# Digital_Isolator.net
KiCad netlist of a schematic drawn in Altium Designer
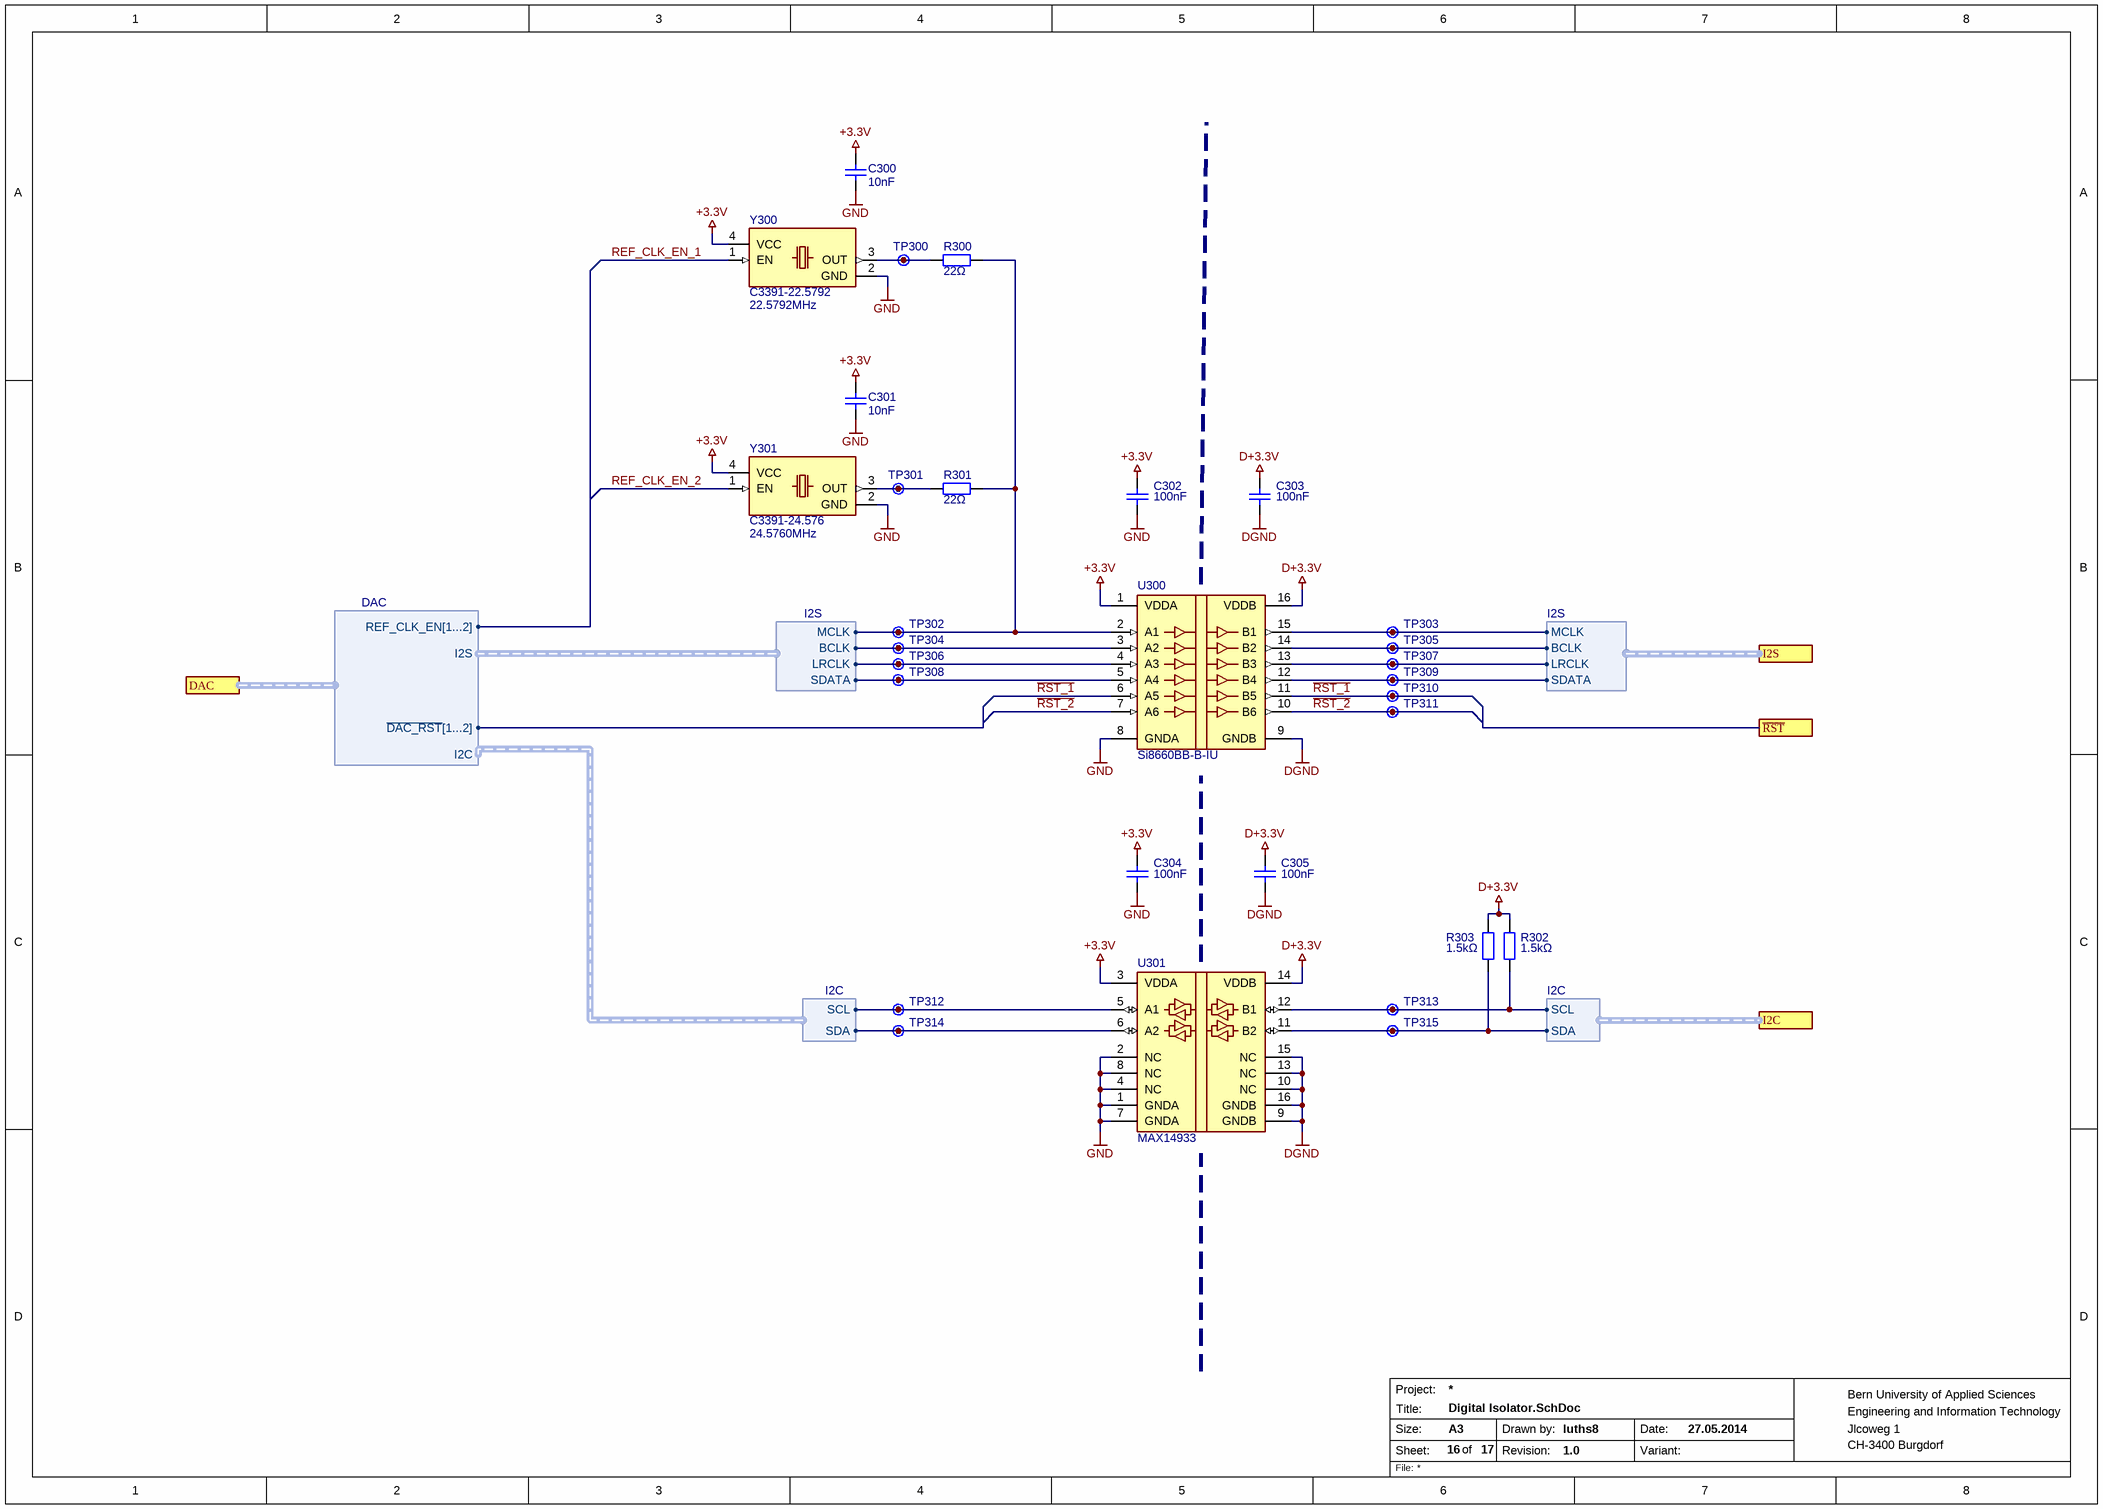
[diagram p0: Digital Isolator.SchDoc]

(export (version "E")
  (design (tool "Eeschema 10.0.6"))
  (components
    (comp (ref "C300")
      (value "10nF")
      (footprint "SMD0603CAP")
      (description "Ceramic Capacitor")
      (libsource (lib "Audio-Streamer") (part "Capacitor Ceramic"))
    )
    (comp (ref "C301")
      (value "10nF")
      (footprint "SMD0603CAP")
      (description "Ceramic Capacitor")
      (libsource (lib "Audio-Streamer") (part "Capacitor Ceramic"))
    )
    (comp (ref "C302")
      (value "100nF")
      (footprint "SMD0603CAP")
      (description "Ceramic Capacitor")
      (libsource (lib "Audio-Streamer") (part "Capacitor Ceramic"))
    )
    (comp (ref "C303")
      (value "100nF")
      (footprint "SMD0603CAP")
      (description "Ceramic Capacitor")
      (libsource (lib "Audio-Streamer") (part "Capacitor Ceramic"))
    )
    (comp (ref "C304")
      (value "100nF")
      (footprint "SMD0603CAP")
      (description "Ceramic Capacitor")
      (libsource (lib "Audio-Streamer") (part "Capacitor Ceramic"))
    )
    (comp (ref "C305")
      (value "100nF")
      (footprint "SMD0603CAP")
      (description "Ceramic Capacitor")
      (libsource (lib "Audio-Streamer") (part "Capacitor Ceramic"))
    )
    (comp (ref "R300")
      (value "22Ω")
      (footprint "SMD0603RES")
      (description "Resistor")
      (libsource (lib "") (part "Resistor_1"))
    )
    (comp (ref "R301")
      (value "22Ω")
      (footprint "SMD0603RES")
      (description "Resistor")
      (libsource (lib "") (part "Resistor_1"))
    )
    (comp (ref "R302")
      (value "1.5kΩ")
      (footprint "SMD0603RES")
      (description "Resistor")
      (libsource (lib "Audio-Streamer") (part "Resistor"))
    )
    (comp (ref "R303")
      (value "1.5kΩ")
      (footprint "SMD0603RES")
      (description "Resistor")
      (libsource (lib "Audio-Streamer") (part "Resistor"))
    )
    (comp (ref "TP300")
      (value "Testpoint")
      (footprint "TP")
      (libsource (lib "Audio-Streamer") (part "Testpoint"))
    )
    (comp (ref "TP301")
      (value "Testpoint")
      (footprint "TP")
      (libsource (lib "Audio-Streamer") (part "Testpoint"))
    )
    (comp (ref "TP302")
      (value "Testpoint")
      (footprint "TP")
      (libsource (lib "Audio-Streamer") (part "Testpoint"))
    )
    (comp (ref "TP303")
      (value "Testpoint")
      (footprint "TP")
      (libsource (lib "Audio-Streamer") (part "Testpoint"))
    )
    (comp (ref "TP304")
      (value "Testpoint")
      (footprint "TP")
      (libsource (lib "Audio-Streamer") (part "Testpoint"))
    )
    (comp (ref "TP305")
      (value "Testpoint")
      (footprint "TP")
      (libsource (lib "Audio-Streamer") (part "Testpoint"))
    )
    (comp (ref "TP306")
      (value "Testpoint")
      (footprint "TP")
      (libsource (lib "Audio-Streamer") (part "Testpoint"))
    )
    (comp (ref "TP307")
      (value "Testpoint")
      (footprint "TP")
      (libsource (lib "Audio-Streamer") (part "Testpoint"))
    )
    (comp (ref "TP308")
      (value "Testpoint")
      (footprint "TP")
      (libsource (lib "Audio-Streamer") (part "Testpoint"))
    )
    (comp (ref "TP309")
      (value "Testpoint")
      (footprint "TP")
      (libsource (lib "Audio-Streamer") (part "Testpoint"))
    )
    (comp (ref "TP310")
      (value "Testpoint")
      (footprint "TP")
      (libsource (lib "Audio-Streamer") (part "Testpoint"))
    )
    (comp (ref "TP311")
      (value "Testpoint")
      (footprint "TP")
      (libsource (lib "Audio-Streamer") (part "Testpoint"))
    )
    (comp (ref "TP312")
      (value "Testpoint")
      (footprint "TP")
      (libsource (lib "Audio-Streamer") (part "Testpoint"))
    )
    (comp (ref "TP313")
      (value "Testpoint")
      (footprint "TP")
      (libsource (lib "Audio-Streamer") (part "Testpoint"))
    )
    (comp (ref "TP314")
      (value "Testpoint")
      (footprint "TP")
      (libsource (lib "Audio-Streamer") (part "Testpoint"))
    )
    (comp (ref "TP315")
      (value "Testpoint")
      (footprint "TP")
      (libsource (lib "Audio-Streamer") (part "Testpoint"))
    )
    (comp (ref "U300")
      (value "Si8660BB-B-IU")
      (footprint "SOIC16WIDE")
      (description "Unidirectional digital isolator")
      (libsource (lib "Audio-Streamer") (part "Si8660BB-B-IU"))
    )
    (comp (ref "U301")
      (value "MAX14933")
      (footprint "SOIC16WIDE")
      (description "Bidirectional digital isolator")
      (libsource (lib "Audio-Streamer") (part "MAX14933"))
    )
    (comp (ref "Y300")
      (value "C3391-22.5792")
      (footprint "OSC_CRYSTEK")
      (description "HCMOS Oscillator")
      (fields (field (name "FREQUENCY") "22.5792MHz"))
      (libsource (lib "Audio-Streamer") (part "Oscillator Crystek"))
    )
    (comp (ref "Y301")
      (value "C3391-24.576")
      (footprint "OSC_CRYSTEK")
      (description "HCMOS Oscillator")
      (fields (field (name "FREQUENCY") "24.5760MHz"))
      (libsource (lib "Audio-Streamer") (part "Oscillator Crystek"))
    )
  )
  (nets
    (net (code "4") (name "+3.3V") (class "Default")
      (node (ref "C300") (pin "1") (pinfunction "1_1") (pintype "passive"))
      (node (ref "C301") (pin "1") (pinfunction "1_1") (pintype "passive"))
      (node (ref "C302") (pin "1") (pinfunction "1_1") (pintype "passive"))
      (node (ref "C304") (pin "1") (pinfunction "1_1") (pintype "passive"))
      (node (ref "U300") (pin "1") (pinfunction "VDDA_1") (pintype "power_in"))
      (node (ref "U301") (pin "3") (pinfunction "VDDA_3") (pintype "power_in"))
      (node (ref "Y300") (pin "4") (pinfunction "VCC_4") (pintype "power_in"))
      (node (ref "Y301") (pin "4") (pinfunction "VCC_4") (pintype "power_in"))
    )
    (net (code "6") (name "/REF_CLK_EN_1") (class "Default")
      (node (ref "Y300") (pin "1") (pinfunction "EN_1") (pintype "input"))
    )
    (net (code "7") (name "/REF_CLK_EN_2") (class "Default")
      (node (ref "Y301") (pin "1") (pinfunction "EN_1") (pintype "input"))
    )
    (net (code "10") (name "/~{RST_1}") (class "Default")
      (node (ref "TP310") (pin "1") (pinfunction "1_1") (pintype "passive"))
      (node (ref "U300") (pin "11") (pinfunction "B5_11") (pintype "output"))
      (node (ref "U300") (pin "6") (pinfunction "A5_6") (pintype "input"))
    )
    (net (code "11") (name "/~{RST_2}") (class "Default")
      (node (ref "TP311") (pin "1") (pinfunction "1_1") (pintype "passive"))
      (node (ref "U300") (pin "10") (pinfunction "B6_10") (pintype "output"))
      (node (ref "U300") (pin "7") (pinfunction "A6_7") (pintype "input"))
    )
    (net (code "13") (name "D+3.3V") (class "Default")
      (node (ref "C303") (pin "1") (pinfunction "1_1") (pintype "passive"))
      (node (ref "C305") (pin "1") (pinfunction "1_1") (pintype "passive"))
      (node (ref "R302") (pin "2") (pinfunction "2_2") (pintype "passive"))
      (node (ref "R303") (pin "2") (pinfunction "2_2") (pintype "passive"))
      (node (ref "U300") (pin "16") (pinfunction "VDDB_16") (pintype "power_in"))
      (node (ref "U301") (pin "14") (pinfunction "VDDB_14") (pintype "power_in"))
    )
    (net (code "14") (name "DGND") (class "Default")
      (node (ref "C303") (pin "2") (pinfunction "q_2") (pintype "passive"))
      (node (ref "C305") (pin "2") (pinfunction "q_2") (pintype "passive"))
      (node (ref "U300") (pin "9") (pinfunction "GNDB_9") (pintype "power_in"))
      (node (ref "U301") (pin "10") (pinfunction "NC_10") (pintype "passive"))
      (node (ref "U301") (pin "13") (pinfunction "NC_13") (pintype "passive"))
      (node (ref "U301") (pin "15") (pinfunction "NC_15") (pintype "passive"))
      (node (ref "U301") (pin "16") (pinfunction "GNDB_16") (pintype "power_in"))
      (node (ref "U301") (pin "9") (pinfunction "GNDB_9") (pintype "power_in"))
    )
    (net (code "15") (name "GND") (class "Default")
      (node (ref "C300") (pin "2") (pinfunction "q_2") (pintype "passive"))
      (node (ref "C301") (pin "2") (pinfunction "q_2") (pintype "passive"))
      (node (ref "C302") (pin "2") (pinfunction "q_2") (pintype "passive"))
      (node (ref "C304") (pin "2") (pinfunction "q_2") (pintype "passive"))
      (node (ref "U300") (pin "8") (pinfunction "GNDA_8") (pintype "power_in"))
      (node (ref "U301") (pin "1") (pinfunction "GNDA_1") (pintype "power_in"))
      (node (ref "U301") (pin "2") (pinfunction "NC_2") (pintype "passive"))
      (node (ref "U301") (pin "4") (pinfunction "NC_4") (pintype "passive"))
      (node (ref "U301") (pin "7") (pinfunction "GNDA_7") (pintype "power_in"))
      (node (ref "U301") (pin "8") (pinfunction "NC_8") (pintype "passive"))
      (node (ref "Y300") (pin "2") (pinfunction "GND_2") (pintype "power_in"))
      (node (ref "Y301") (pin "2") (pinfunction "GND_2") (pintype "power_in"))
    )
    (net (code "16") (name "Net-(U300-A1)") (class "Default")
      (node (ref "R300") (pin "2") (pinfunction "2_2") (pintype "passive"))
      (node (ref "R301") (pin "2") (pinfunction "2_2") (pintype "passive"))
      (node (ref "TP302") (pin "1") (pinfunction "1_1") (pintype "passive"))
      (node (ref "U300") (pin "2") (pinfunction "A1_2") (pintype "input"))
    )
    (net (code "17") (name "Net-(U300-A2)") (class "Default")
      (node (ref "TP304") (pin "1") (pinfunction "1_1") (pintype "passive"))
      (node (ref "U300") (pin "3") (pinfunction "A2_3") (pintype "input"))
    )
    (net (code "18") (name "Net-(U300-A3)") (class "Default")
      (node (ref "TP306") (pin "1") (pinfunction "1_1") (pintype "passive"))
      (node (ref "U300") (pin "4") (pinfunction "A3_4") (pintype "input"))
    )
    (net (code "19") (name "Net-(U300-A4)") (class "Default")
      (node (ref "TP308") (pin "1") (pinfunction "1_1") (pintype "passive"))
      (node (ref "U300") (pin "5") (pinfunction "A4_5") (pintype "input"))
    )
    (net (code "20") (name "Net-(U300-B1)") (class "Default")
      (node (ref "TP303") (pin "1") (pinfunction "1_1") (pintype "passive"))
      (node (ref "U300") (pin "15") (pinfunction "B1_15") (pintype "output"))
    )
    (net (code "21") (name "Net-(U300-B2)") (class "Default")
      (node (ref "TP305") (pin "1") (pinfunction "1_1") (pintype "passive"))
      (node (ref "U300") (pin "14") (pinfunction "B2_14") (pintype "output"))
    )
    (net (code "22") (name "Net-(U300-B3)") (class "Default")
      (node (ref "TP307") (pin "1") (pinfunction "1_1") (pintype "passive"))
      (node (ref "U300") (pin "13") (pinfunction "B3_13") (pintype "output"))
    )
    (net (code "23") (name "Net-(U300-B4)") (class "Default")
      (node (ref "TP309") (pin "1") (pinfunction "1_1") (pintype "passive"))
      (node (ref "U300") (pin "12") (pinfunction "B4_12") (pintype "output"))
    )
    (net (code "24") (name "Net-(U301-A1)") (class "Default")
      (node (ref "TP312") (pin "1") (pinfunction "1_1") (pintype "passive"))
      (node (ref "U301") (pin "5") (pinfunction "A1_5") (pintype "bidirectional"))
    )
    (net (code "25") (name "Net-(U301-A2)") (class "Default")
      (node (ref "TP314") (pin "1") (pinfunction "1_1") (pintype "passive"))
      (node (ref "U301") (pin "6") (pinfunction "A2_6") (pintype "bidirectional"))
    )
    (net (code "26") (name "Net-(U301-B1)") (class "Default")
      (node (ref "R302") (pin "1") (pinfunction "1_1") (pintype "passive"))
      (node (ref "TP313") (pin "1") (pinfunction "1_1") (pintype "passive"))
      (node (ref "U301") (pin "12") (pinfunction "B1_12") (pintype "bidirectional"))
    )
    (net (code "27") (name "Net-(U301-B2)") (class "Default")
      (node (ref "R303") (pin "1") (pinfunction "1_1") (pintype "passive"))
      (node (ref "TP315") (pin "1") (pinfunction "1_1") (pintype "passive"))
      (node (ref "U301") (pin "11") (pinfunction "B2_11") (pintype "bidirectional"))
    )
    (net (code "28") (name "Net-(Y300-OUT)") (class "Default")
      (node (ref "R300") (pin "1") (pinfunction "1_1") (pintype "passive"))
      (node (ref "TP300") (pin "1") (pinfunction "1_1") (pintype "passive"))
      (node (ref "Y300") (pin "3") (pinfunction "OUT_3") (pintype "output"))
    )
    (net (code "29") (name "Net-(Y301-OUT)") (class "Default")
      (node (ref "R301") (pin "1") (pinfunction "1_1") (pintype "passive"))
      (node (ref "TP301") (pin "1") (pinfunction "1_1") (pintype "passive"))
      (node (ref "Y301") (pin "3") (pinfunction "OUT_3") (pintype "output"))
    )
  )
)
